# M5stampS3_round_lcd.net
KiCad netlist of a schematic drawn in EAGLE
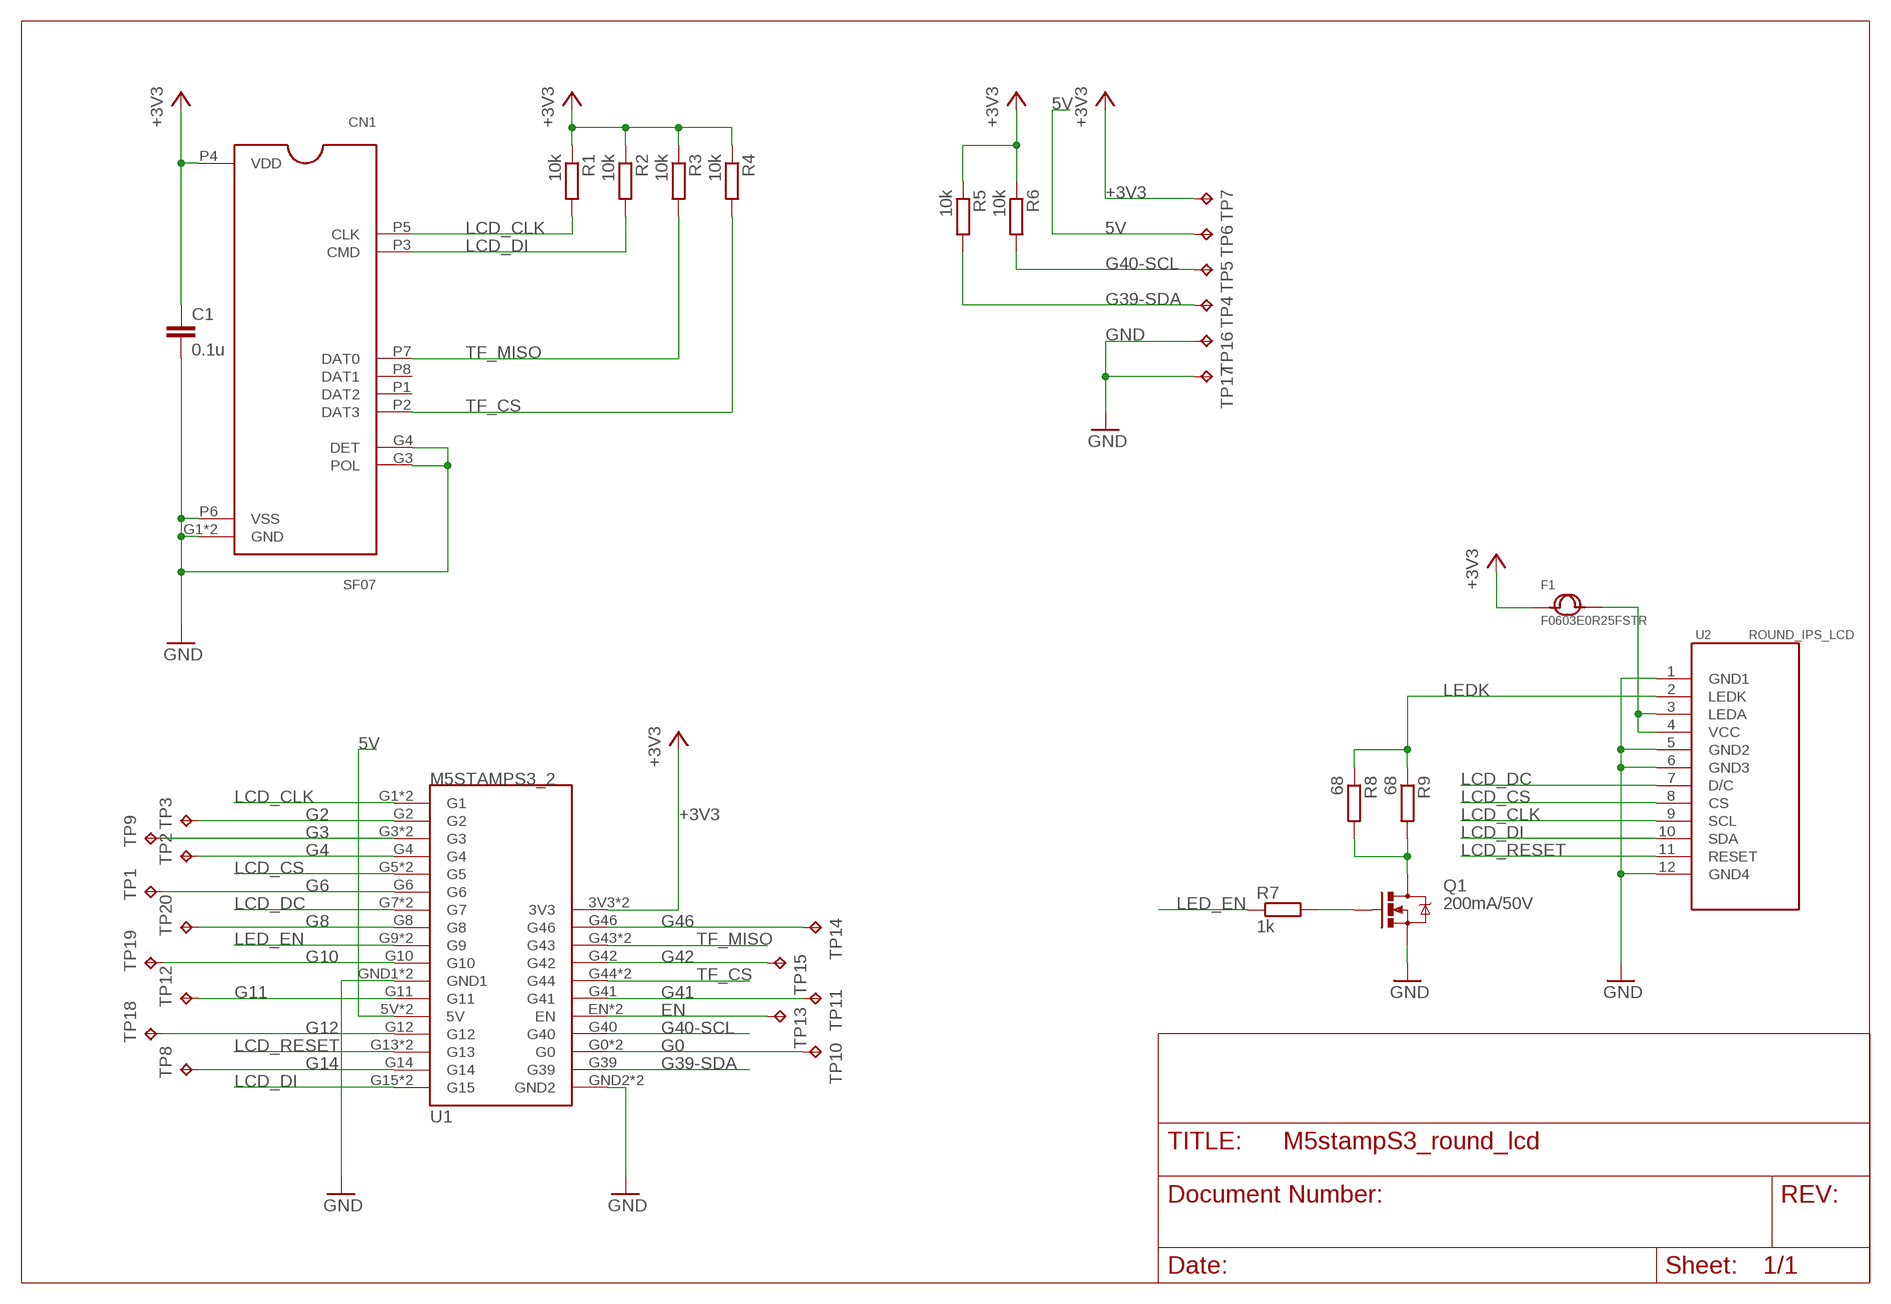
[diagram p0: schematic, sheet 1]

(export (version "E")
  (design (tool "Eeschema 10.0.6"))
  (components
    (comp (ref "C1")
      (value "0.1u")
      (footprint "eagle-import:C0603")
      (libsource (lib "eagle-import") (part "C-EUC0603"))
    )
    (comp (ref "CN1")
      (value "SF07")
      (footprint "eagle-import:POS-8")
      (fields (field (name "MF") "Molex") (field (name "MP") "47579-0001"))
      (libsource (lib "eagle-import") (part "SF07"))
    )
    (comp (ref "F1")
      (value "F0603E0R25FSTR")
      (footprint "eagle-import:C0603")
      (libsource (lib "eagle-import") (part "FUSE0603"))
    )
    (comp (ref "Q1")
      (value "200mA/50V")
      (footprint "eagle-import:SOT23-3")
      (libsource (lib "eagle-import") (part "MOSFET-NCHANNELBSS138"))
    )
    (comp (ref "R1")
      (value "10k")
      (footprint "eagle-import:R0603")
      (libsource (lib "eagle-import") (part "R-EU_R0603"))
    )
    (comp (ref "R2")
      (value "10k")
      (footprint "eagle-import:R0603")
      (libsource (lib "eagle-import") (part "R-EU_R0603"))
    )
    (comp (ref "R3")
      (value "10k")
      (footprint "eagle-import:R0603")
      (libsource (lib "eagle-import") (part "R-EU_R0603"))
    )
    (comp (ref "R4")
      (value "10k")
      (footprint "eagle-import:R0603")
      (libsource (lib "eagle-import") (part "R-EU_R0603"))
    )
    (comp (ref "R5")
      (value "10k")
      (footprint "eagle-import:R0603")
      (libsource (lib "eagle-import") (part "R-EU_R0603"))
    )
    (comp (ref "R6")
      (value "10k")
      (footprint "eagle-import:R0603")
      (libsource (lib "eagle-import") (part "R-EU_R0603"))
    )
    (comp (ref "R7")
      (value "1k")
      (footprint "eagle-import:R0603")
      (libsource (lib "eagle-import") (part "R-EU_R0603"))
    )
    (comp (ref "R8")
      (value "68")
      (footprint "eagle-import:R0603")
      (libsource (lib "eagle-import") (part "R-EU_R0603"))
    )
    (comp (ref "R9")
      (value "68")
      (footprint "eagle-import:R0603")
      (libsource (lib "eagle-import") (part "R-EU_R0603"))
    )
    (comp (ref "TP1")
      (value "TPTP18R")
      (footprint "eagle-import:TP18R")
      (libsource (lib "eagle-import") (part "TPTP18R"))
    )
    (comp (ref "TP2")
      (value "TPTP18R")
      (footprint "eagle-import:TP18R")
      (libsource (lib "eagle-import") (part "TPTP18R"))
    )
    (comp (ref "TP3")
      (value "TPTP18R")
      (footprint "eagle-import:TP18R")
      (libsource (lib "eagle-import") (part "TPTP18R"))
    )
    (comp (ref "TP4")
      (value "TPTP18R")
      (footprint "eagle-import:TP18R")
      (libsource (lib "eagle-import") (part "TPTP18R"))
    )
    (comp (ref "TP5")
      (value "TPTP18R")
      (footprint "eagle-import:TP18R")
      (libsource (lib "eagle-import") (part "TPTP18R"))
    )
    (comp (ref "TP6")
      (value "TPTP18R")
      (footprint "eagle-import:TP18R")
      (libsource (lib "eagle-import") (part "TPTP18R"))
    )
    (comp (ref "TP7")
      (value "TPTP18R")
      (footprint "eagle-import:TP18R")
      (libsource (lib "eagle-import") (part "TPTP18R"))
    )
    (comp (ref "TP8")
      (value "TPTP18R")
      (footprint "eagle-import:TP18R")
      (libsource (lib "eagle-import") (part "TPTP18R"))
    )
    (comp (ref "TP9")
      (value "TPTP18R")
      (footprint "eagle-import:TP18R")
      (libsource (lib "eagle-import") (part "TPTP18R"))
    )
    (comp (ref "TP10")
      (value "TPTP18R")
      (footprint "eagle-import:TP18R")
      (libsource (lib "eagle-import") (part "TPTP18R"))
    )
    (comp (ref "TP11")
      (value "TPTP18R")
      (footprint "eagle-import:TP18R")
      (libsource (lib "eagle-import") (part "TPTP18R"))
    )
    (comp (ref "TP12")
      (value "TPTP18R")
      (footprint "eagle-import:TP18R")
      (libsource (lib "eagle-import") (part "TPTP18R"))
    )
    (comp (ref "TP13")
      (value "TPTP18R")
      (footprint "eagle-import:TP18R")
      (libsource (lib "eagle-import") (part "TPTP18R"))
    )
    (comp (ref "TP14")
      (value "TPTP18R")
      (footprint "eagle-import:TP18R")
      (libsource (lib "eagle-import") (part "TPTP18R"))
    )
    (comp (ref "TP15")
      (value "TPTP18R")
      (footprint "eagle-import:TP18R")
      (libsource (lib "eagle-import") (part "TPTP18R"))
    )
    (comp (ref "TP16")
      (value "TPTP18R")
      (footprint "eagle-import:TP18R")
      (libsource (lib "eagle-import") (part "TPTP18R"))
    )
    (comp (ref "TP17")
      (value "TPTP18R")
      (footprint "eagle-import:TP18R")
      (libsource (lib "eagle-import") (part "TPTP18R"))
    )
    (comp (ref "TP18")
      (value "TPTP18R")
      (footprint "eagle-import:TP18R")
      (libsource (lib "eagle-import") (part "TPTP18R"))
    )
    (comp (ref "TP19")
      (value "TPTP18R")
      (footprint "eagle-import:TP18R")
      (libsource (lib "eagle-import") (part "TPTP18R"))
    )
    (comp (ref "TP20")
      (value "TPTP18R")
      (footprint "eagle-import:TP18R")
      (libsource (lib "eagle-import") (part "TPTP18R"))
    )
    (comp (ref "U1")
      (value "M5STAMPS3_2")
      (footprint "eagle-import:M5STAMPS3_2")
      (libsource (lib "eagle-import") (part "M5STAMPS3_2"))
    )
    (comp (ref "U2")
      (value "ROUND_IPS_LCD")
      (footprint "eagle-import:ROUND_IPS_LCD")
      (libsource (lib "eagle-import") (part "ROUND_IPS_LCD"))
    )
  )
  (nets
    (net (code "1") (name "+3V3") (class "Default")
      (node (ref "C1") (pin "1") (pinfunction "1_1") (pintype "passive"))
      (node (ref "CN1") (pin "P4") (pinfunction "VDD_P4") (pintype "power_in"))
      (node (ref "F1") (pin "1") (pinfunction "1_1") (pintype "bidirectional"))
      (node (ref "R1") (pin "1") (pinfunction "1_1") (pintype "passive"))
      (node (ref "R2") (pin "1") (pinfunction "1_1") (pintype "passive"))
      (node (ref "R3") (pin "1") (pinfunction "1_1") (pintype "passive"))
      (node (ref "R4") (pin "1") (pinfunction "1_1") (pintype "passive"))
      (node (ref "R5") (pin "1") (pinfunction "1_1") (pintype "passive"))
      (node (ref "R6") (pin "1") (pinfunction "1_1") (pintype "passive"))
      (node (ref "TP7") (pin "TP") (pinfunction "TP_TP") (pintype "input"))
      (node (ref "U1") (pin "3V3") (pinfunction "3V3_3V3") (pintype "power_in"))
      (node (ref "U1") (pin "3V3_") (pinfunction "3V3_3V3_") (pintype "power_in"))
    )
    (net (code "2") (name "/5V") (class "Default")
      (node (ref "TP6") (pin "TP") (pinfunction "TP_TP") (pintype "input"))
      (node (ref "U1") (pin "5V") (pinfunction "5V_5V") (pintype "power_in"))
      (node (ref "U1") (pin "5V_") (pinfunction "5V_5V_") (pintype "power_in"))
    )
    (net (code "3") (name "/EN") (class "Default")
      (node (ref "TP13") (pin "TP") (pinfunction "TP_TP") (pintype "input"))
      (node (ref "U1") (pin "EN") (pinfunction "EN_EN") (pintype "input"))
      (node (ref "U1") (pin "EN_") (pinfunction "EN_EN_") (pintype "input"))
    )
    (net (code "4") (name "/G0") (class "Default")
      (node (ref "TP10") (pin "TP") (pinfunction "TP_TP") (pintype "input"))
      (node (ref "U1") (pin "G0") (pinfunction "G0_G0") (pintype "bidirectional"))
      (node (ref "U1") (pin "G0_") (pinfunction "G0_G0_") (pintype "bidirectional"))
    )
    (net (code "5") (name "/G2") (class "Default")
      (node (ref "TP3") (pin "TP") (pinfunction "TP_TP") (pintype "input"))
      (node (ref "U1") (pin "G2") (pinfunction "G2_G2") (pintype "bidirectional"))
    )
    (net (code "6") (name "/G3") (class "Default")
      (node (ref "TP9") (pin "TP") (pinfunction "TP_TP") (pintype "input"))
      (node (ref "U1") (pin "G3") (pinfunction "G3_G3") (pintype "bidirectional"))
      (node (ref "U1") (pin "G3_") (pinfunction "G3_G3_") (pintype "bidirectional"))
    )
    (net (code "7") (name "/G4") (class "Default")
      (node (ref "TP2") (pin "TP") (pinfunction "TP_TP") (pintype "input"))
      (node (ref "U1") (pin "G4") (pinfunction "G4_G4") (pintype "bidirectional"))
    )
    (net (code "8") (name "/G6") (class "Default")
      (node (ref "TP1") (pin "TP") (pinfunction "TP_TP") (pintype "input"))
      (node (ref "U1") (pin "G6") (pinfunction "G6_G6") (pintype "bidirectional"))
    )
    (net (code "9") (name "/G8") (class "Default")
      (node (ref "TP20") (pin "TP") (pinfunction "TP_TP") (pintype "input"))
      (node (ref "U1") (pin "G8") (pinfunction "G8_G8") (pintype "bidirectional"))
    )
    (net (code "10") (name "/G10") (class "Default")
      (node (ref "TP19") (pin "TP") (pinfunction "TP_TP") (pintype "input"))
      (node (ref "U1") (pin "G10") (pinfunction "G10_G10") (pintype "bidirectional"))
    )
    (net (code "11") (name "/G11") (class "Default")
      (node (ref "TP12") (pin "TP") (pinfunction "TP_TP") (pintype "input"))
      (node (ref "U1") (pin "G11") (pinfunction "G11_G11") (pintype "bidirectional"))
    )
    (net (code "12") (name "/G12") (class "Default")
      (node (ref "TP18") (pin "TP") (pinfunction "TP_TP") (pintype "input"))
      (node (ref "U1") (pin "G12") (pinfunction "G12_G12") (pintype "bidirectional"))
    )
    (net (code "13") (name "/G14") (class "Default")
      (node (ref "TP8") (pin "TP") (pinfunction "TP_TP") (pintype "input"))
      (node (ref "U1") (pin "G14") (pinfunction "G14_G14") (pintype "bidirectional"))
    )
    (net (code "14") (name "/G39-SDA") (class "Default")
      (node (ref "R5") (pin "2") (pinfunction "2_2") (pintype "passive"))
      (node (ref "TP4") (pin "TP") (pinfunction "TP_TP") (pintype "input"))
      (node (ref "U1") (pin "G39") (pinfunction "G39_G39") (pintype "bidirectional"))
    )
    (net (code "15") (name "/G40-SCL") (class "Default")
      (node (ref "R6") (pin "2") (pinfunction "2_2") (pintype "passive"))
      (node (ref "TP5") (pin "TP") (pinfunction "TP_TP") (pintype "input"))
      (node (ref "U1") (pin "G40") (pinfunction "G40_G40") (pintype "bidirectional"))
    )
    (net (code "16") (name "/G41") (class "Default")
      (node (ref "TP11") (pin "TP") (pinfunction "TP_TP") (pintype "input"))
      (node (ref "U1") (pin "G41") (pinfunction "G41_G41") (pintype "bidirectional"))
    )
    (net (code "17") (name "/G42") (class "Default")
      (node (ref "TP15") (pin "TP") (pinfunction "TP_TP") (pintype "input"))
      (node (ref "U1") (pin "G42") (pinfunction "G42_G42") (pintype "bidirectional"))
    )
    (net (code "18") (name "/G46") (class "Default")
      (node (ref "TP14") (pin "TP") (pinfunction "TP_TP") (pintype "input"))
      (node (ref "U1") (pin "G46") (pinfunction "G46_G46") (pintype "bidirectional"))
    )
    (net (code "19") (name "/LCD_CLK") (class "Default")
      (node (ref "CN1") (pin "P5") (pinfunction "CLK_P5") (pintype "input"))
      (node (ref "R1") (pin "2") (pinfunction "2_2") (pintype "passive"))
      (node (ref "U1") (pin "G1") (pinfunction "G1_G1") (pintype "bidirectional"))
      (node (ref "U1") (pin "G1_") (pinfunction "G1_G1_") (pintype "bidirectional"))
      (node (ref "U2") (pin "9") (pinfunction "SCL_9") (pintype "input"))
    )
    (net (code "20") (name "/LCD_CS") (class "Default")
      (node (ref "U1") (pin "G5") (pinfunction "G5_G5") (pintype "bidirectional"))
      (node (ref "U1") (pin "G5_") (pinfunction "G5_G5_") (pintype "bidirectional"))
      (node (ref "U2") (pin "8") (pinfunction "CS_8") (pintype "input"))
    )
    (net (code "21") (name "/LCD_DC") (class "Default")
      (node (ref "U1") (pin "G7") (pinfunction "G7_G7") (pintype "bidirectional"))
      (node (ref "U1") (pin "G7_") (pinfunction "G7_G7_") (pintype "bidirectional"))
      (node (ref "U2") (pin "7") (pinfunction "D/C_7") (pintype "input"))
    )
    (net (code "22") (name "/LCD_DI") (class "Default")
      (node (ref "CN1") (pin "P3") (pinfunction "CMD_P3") (pintype "input"))
      (node (ref "R2") (pin "2") (pinfunction "2_2") (pintype "passive"))
      (node (ref "U1") (pin "G15") (pinfunction "G15_G15") (pintype "bidirectional"))
      (node (ref "U1") (pin "G15_") (pinfunction "G15_G15_") (pintype "bidirectional"))
      (node (ref "U2") (pin "10") (pinfunction "SDA_10") (pintype "bidirectional"))
    )
    (net (code "23") (name "/LCD_RESET") (class "Default")
      (node (ref "U1") (pin "G13") (pinfunction "G13_G13") (pintype "bidirectional"))
      (node (ref "U1") (pin "G13_") (pinfunction "G13_G13_") (pintype "bidirectional"))
      (node (ref "U2") (pin "11") (pinfunction "RESET_11") (pintype "input"))
    )
    (net (code "24") (name "/LEDK") (class "Default")
      (node (ref "R8") (pin "1") (pinfunction "1_1") (pintype "passive"))
      (node (ref "R9") (pin "1") (pinfunction "1_1") (pintype "passive"))
      (node (ref "U2") (pin "2") (pinfunction "LEDK_2") (pintype "bidirectional"))
    )
    (net (code "25") (name "/LED_EN") (class "Default")
      (node (ref "R7") (pin "1") (pinfunction "1_1") (pintype "passive"))
      (node (ref "U1") (pin "G9") (pinfunction "G9_G9") (pintype "bidirectional"))
      (node (ref "U1") (pin "G9_") (pinfunction "G9_G9_") (pintype "bidirectional"))
    )
    (net (code "26") (name "/TF_CS") (class "Default")
      (node (ref "CN1") (pin "P2") (pinfunction "DAT3_P2") (pintype "bidirectional"))
      (node (ref "R4") (pin "2") (pinfunction "2_2") (pintype "passive"))
      (node (ref "U1") (pin "G44") (pinfunction "G44_G44") (pintype "bidirectional"))
      (node (ref "U1") (pin "G44_") (pinfunction "G44_G44_") (pintype "bidirectional"))
    )
    (net (code "27") (name "/TF_MISO") (class "Default")
      (node (ref "CN1") (pin "P7") (pinfunction "DAT0_P7") (pintype "bidirectional"))
      (node (ref "R3") (pin "2") (pinfunction "2_2") (pintype "passive"))
      (node (ref "U1") (pin "G43") (pinfunction "G43_G43") (pintype "bidirectional"))
      (node (ref "U1") (pin "G43_") (pinfunction "G43_G43_") (pintype "bidirectional"))
    )
    (net (code "28") (name "GND") (class "Default")
      (node (ref "C1") (pin "2") (pinfunction "2_2") (pintype "passive"))
      (node (ref "CN1") (pin "G1") (pinfunction "GND_G1") (pintype "passive"))
      (node (ref "CN1") (pin "G2") (pinfunction "GND_G2") (pintype "passive"))
      (node (ref "CN1") (pin "G3") (pinfunction "POL_G3") (pintype "passive"))
      (node (ref "CN1") (pin "G4") (pinfunction "DET_G4") (pintype "passive"))
      (node (ref "CN1") (pin "P6") (pinfunction "VSS_P6") (pintype "passive"))
      (node (ref "Q1") (pin "2") (pinfunction "S_2") (pintype "passive"))
      (node (ref "TP16") (pin "TP") (pinfunction "TP_TP") (pintype "input"))
      (node (ref "TP17") (pin "TP") (pinfunction "TP_TP") (pintype "input"))
      (node (ref "U1") (pin "GND1") (pinfunction "GND1_GND1") (pintype "power_in"))
      (node (ref "U1") (pin "GND1_") (pinfunction "GND1_GND1_") (pintype "power_in"))
      (node (ref "U1") (pin "GND2") (pinfunction "GND2_GND2") (pintype "power_in"))
      (node (ref "U1") (pin "GND2_") (pinfunction "GND2_GND2_") (pintype "power_in"))
      (node (ref "U2") (pin "1") (pinfunction "GND1_1") (pintype "power_in"))
      (node (ref "U2") (pin "12") (pinfunction "GND4_12") (pintype "power_in"))
      (node (ref "U2") (pin "5") (pinfunction "GND2_5") (pintype "power_in"))
      (node (ref "U2") (pin "6") (pinfunction "GND3_6") (pintype "power_in"))
    )
    (net (code "29") (name "Net-(Q1-D)") (class "Default")
      (node (ref "Q1") (pin "3") (pinfunction "D_3") (pintype "passive"))
      (node (ref "R8") (pin "2") (pinfunction "2_2") (pintype "passive"))
      (node (ref "R9") (pin "2") (pinfunction "2_2") (pintype "passive"))
    )
    (net (code "30") (name "Net-(Q1-G)") (class "Default")
      (node (ref "Q1") (pin "1") (pinfunction "G_1") (pintype "passive"))
      (node (ref "R7") (pin "2") (pinfunction "2_2") (pintype "passive"))
    )
    (net (code "31") (name "Net-(U2-LEDA)") (class "Default")
      (node (ref "F1") (pin "2") (pinfunction "2_2") (pintype "bidirectional"))
      (node (ref "U2") (pin "3") (pinfunction "LEDA_3") (pintype "bidirectional"))
      (node (ref "U2") (pin "4") (pinfunction "VCC_4") (pintype "power_in"))
    )
    (net (code "32") (name "unconnected-(CN1-DAT1-PadP8)") (class "Default")
      (node (ref "CN1") (pin "P8") (pinfunction "DAT1_P8") (pintype "bidirectional"))
    )
    (net (code "33") (name "unconnected-(CN1-DAT2-PadP1)") (class "Default")
      (node (ref "CN1") (pin "P1") (pinfunction "DAT2_P1") (pintype "bidirectional"))
    )
  )
)
